# Buttons.net
KiCad netlist of a schematic drawn in Altium Designer
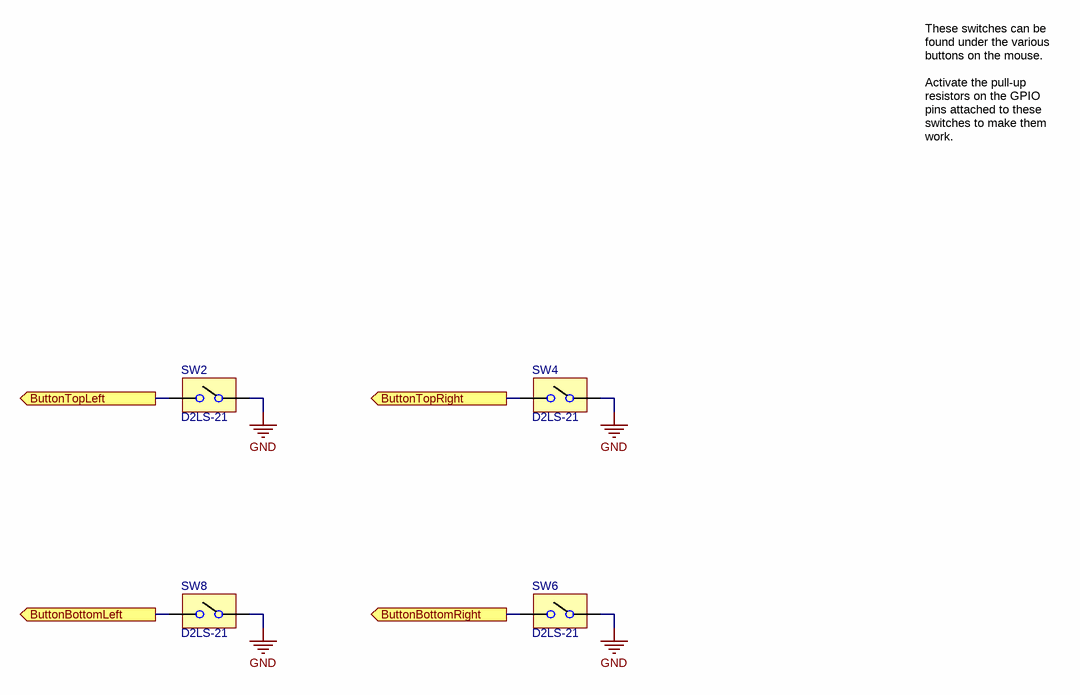
[diagram p0: Buttons.SchDoc]

(export (version "E")
  (design (tool "Eeschema 10.0.6"))
  (components
    (comp (ref "SW2")
      (value "D2LS-21")
      (footprint "D2LS-21")
      (description "Compact Surface-mounting Switch for long durability")
      (libsource (lib "Switches") (part "D2LS-21"))
    )
    (comp (ref "SW4")
      (value "D2LS-21")
      (footprint "D2LS-21")
      (description "Compact Surface-mounting Switch for long durability")
      (libsource (lib "Switches") (part "D2LS-21"))
    )
    (comp (ref "SW6")
      (value "D2LS-21")
      (footprint "D2LS-21")
      (description "Compact Surface-mounting Switch for long durability")
      (libsource (lib "Switches") (part "D2LS-21"))
    )
    (comp (ref "SW8")
      (value "D2LS-21")
      (footprint "D2LS-21")
      (description "Compact Surface-mounting Switch for long durability")
      (libsource (lib "Switches") (part "D2LS-21"))
    )
  )
  (nets
    (net (code "1") (name "/ButtonBottomLeft") (class "Default")
      (node (ref "SW8") (pin "B") (pinfunction "B_B") (pintype "passive"))
    )
    (net (code "2") (name "/ButtonBottomRight") (class "Default")
      (node (ref "SW6") (pin "B") (pinfunction "B_B") (pintype "passive"))
    )
    (net (code "3") (name "/ButtonTopLeft") (class "Default")
      (node (ref "SW2") (pin "B") (pinfunction "B_B") (pintype "passive"))
    )
    (net (code "4") (name "/ButtonTopRight") (class "Default")
      (node (ref "SW4") (pin "B") (pinfunction "B_B") (pintype "passive"))
    )
    (net (code "5") (name "GND") (class "Default")
      (node (ref "SW2") (pin "A") (pinfunction "A_A") (pintype "passive"))
      (node (ref "SW4") (pin "A") (pinfunction "A_A") (pintype "passive"))
      (node (ref "SW6") (pin "A") (pinfunction "A_A") (pintype "passive"))
      (node (ref "SW8") (pin "A") (pinfunction "A_A") (pintype "passive"))
    )
  )
)
